# MCU.net
KiCad netlist of a schematic drawn in Altium Designer
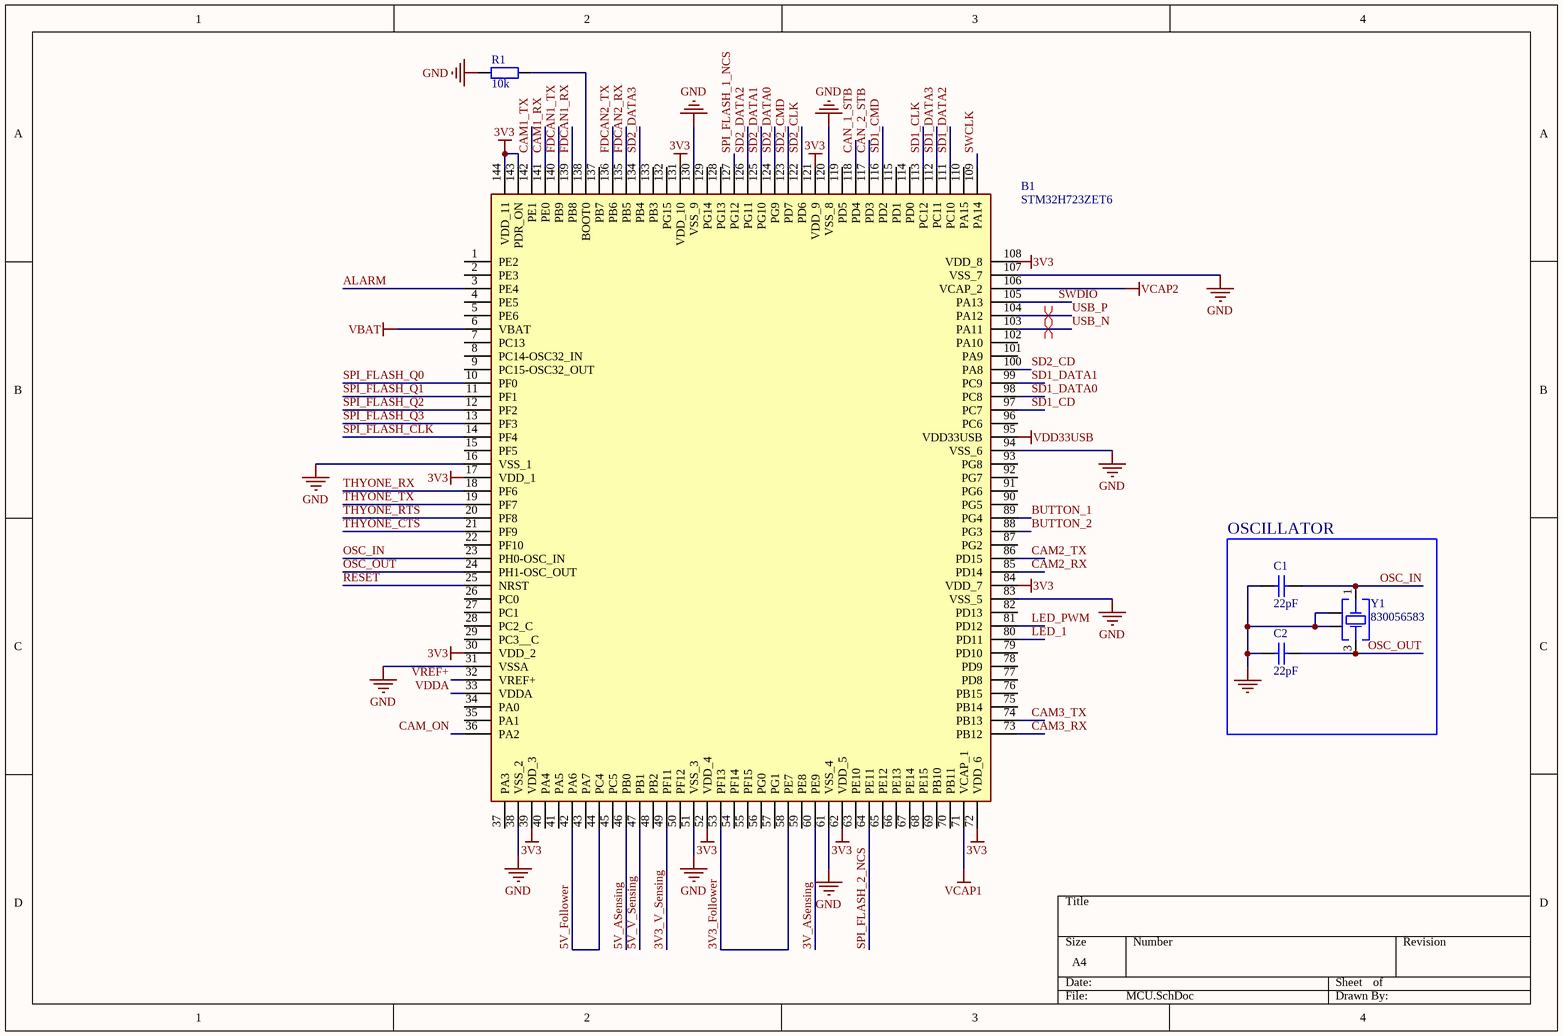
[diagram p0: MCU.SchDoc]

(export (version "E")
  (design (tool "Eeschema 10.0.6"))
  (components
    (comp (ref "B1")
      (value "STM32H723ZET6")
      (footprint "QFP50P2200X2200X160-144N")
      (fields (field (name "MOUSER PART NUMBER") "511-STM32H723ZET6"))
      (libsource (lib "LEEM UPM") (part "STM32H723ZET6"))
    )
    (comp (ref "C1")
      (value "22pF")
      (footprint "WCAP-CSGP_0603_L1.6W0.8H0.8_Reflow")
      (description "WCAP-CSGP Multilayer Ceramic Chip Capacitor, General Purpose, size 0603, NP0, 22pF, 25VDC")
      (fields
        (field (name "MANUFACTURER") "Wurth Elektronik")
        (field (name "MANUFACTURER PART NUMBER") "885012006034")
      )
      (libsource (lib "LEEM UPM") (part "885012209047R"))
    )
    (comp (ref "C2")
      (value "22pF")
      (footprint "WCAP-CSGP_0603_L1.6W0.8H0.8_Reflow")
      (description "WCAP-CSGP Multilayer Ceramic Chip Capacitor, General Purpose, size 0603, NP0, 22pF, 25VDC")
      (fields
        (field (name "MANUFACTURER") "Wurth Elektronik")
        (field (name "MANUFACTURER PART NUMBER") "885012006034")
      )
      (libsource (lib "LEEM UPM") (part "885012209047R"))
    )
    (comp (ref "R1")
      (value "10k")
      (footprint "WRIS-RSKS_0603_Reflow")
      (description "WRIS-RSKS Thick Film Resistor, size 0603, 10000Ohm, 100mW")
      (fields
        (field (name "MANUFACTURER") "Wurth Elektronik")
        (field (name "MANUFACTURER PART NUMBER") "560112116005")
      )
      (libsource (lib "LEEM UPM") (part "560112140010"))
    )
    (comp (ref "Y1")
      (value "830056583")
      (footprint "WE-XTAL_CFPX-104")
      (description "WE-XTAL Quartz Crystal, SMT, CFPX-104, 10MHz, +/-30ppm")
      (fields (field (name "MANUFACTURER") "Wurth Elektronik"))
      (libsource (lib "LEEM UPM") (part "830108161901"))
    )
  )
  (nets
    (net (code "1") (name "/3V3_Follower") (class "Default")
      (node (ref "B1") (pin "53") (pinfunction "PF13_53") (pintype "passive"))
      (node (ref "B1") (pin "58") (pinfunction "PE7_58") (pintype "passive"))
    )
    (net (code "2") (name "/3V3_V_Sensing") (class "Default")
      (node (ref "B1") (pin "49") (pinfunction "PF11_49") (pintype "passive"))
    )
    (net (code "3") (name "/3V_ASensing") (class "Default")
      (node (ref "B1") (pin "60") (pinfunction "PE9_60") (pintype "passive"))
    )
    (net (code "4") (name "/5V_ASensing") (class "Default")
      (node (ref "B1") (pin "46") (pinfunction "PB0_46") (pintype "passive"))
    )
    (net (code "5") (name "/5V_Follower") (class "Default")
      (node (ref "B1") (pin "42") (pinfunction "PA6_42") (pintype "passive"))
      (node (ref "B1") (pin "44") (pinfunction "PC4_44") (pintype "passive"))
    )
    (net (code "6") (name "/5V_V_Sensing") (class "Default")
      (node (ref "B1") (pin "47") (pinfunction "PB1_47") (pintype "passive"))
    )
    (net (code "7") (name "/ALARM") (class "Default")
      (node (ref "B1") (pin "3") (pinfunction "PE4_3") (pintype "passive"))
    )
    (net (code "8") (name "/BUTTON_1") (class "Default")
      (node (ref "B1") (pin "89") (pinfunction "PG4_89") (pintype "passive"))
    )
    (net (code "9") (name "/BUTTON_2") (class "Default")
      (node (ref "B1") (pin "88") (pinfunction "PG3_88") (pintype "passive"))
    )
    (net (code "10") (name "/CAM1_RX") (class "Default")
      (node (ref "B1") (pin "141") (pinfunction "PE0_141") (pintype "passive"))
    )
    (net (code "11") (name "/CAM1_TX") (class "Default")
      (node (ref "B1") (pin "142") (pinfunction "PE1_142") (pintype "passive"))
    )
    (net (code "12") (name "/CAM2_RX") (class "Default")
      (node (ref "B1") (pin "85") (pinfunction "PD14_85") (pintype "passive"))
    )
    (net (code "13") (name "/CAM2_TX") (class "Default")
      (node (ref "B1") (pin "86") (pinfunction "PD15_86") (pintype "passive"))
    )
    (net (code "14") (name "/CAM3_RX") (class "Default")
      (node (ref "B1") (pin "73") (pinfunction "PB12_73") (pintype "passive"))
    )
    (net (code "15") (name "/CAM3_TX") (class "Default")
      (node (ref "B1") (pin "74") (pinfunction "PB13_74") (pintype "passive"))
    )
    (net (code "16") (name "/CAM_ON") (class "Default")
      (node (ref "B1") (pin "36") (pinfunction "PA2_36") (pintype "passive"))
    )
    (net (code "17") (name "/CAN_1_STB") (class "Default")
      (node (ref "B1") (pin "118") (pinfunction "PD4_118") (pintype "passive"))
    )
    (net (code "18") (name "/CAN_2_STB") (class "Default")
      (node (ref "B1") (pin "117") (pinfunction "PD3_117") (pintype "passive"))
    )
    (net (code "19") (name "/FDCAN1_RX") (class "Default")
      (node (ref "B1") (pin "139") (pinfunction "PB8_139") (pintype "passive"))
    )
    (net (code "20") (name "/FDCAN1_TX") (class "Default")
      (node (ref "B1") (pin "140") (pinfunction "PB9_140") (pintype "passive"))
    )
    (net (code "21") (name "/FDCAN2_RX") (class "Default")
      (node (ref "B1") (pin "135") (pinfunction "PB5_135") (pintype "passive"))
    )
    (net (code "22") (name "/FDCAN2_TX") (class "Default")
      (node (ref "B1") (pin "136") (pinfunction "PB6_136") (pintype "passive"))
    )
    (net (code "23") (name "/LED_1") (class "Default")
      (node (ref "B1") (pin "80") (pinfunction "PD11_80") (pintype "passive"))
    )
    (net (code "24") (name "/LED_PWM") (class "Default")
      (node (ref "B1") (pin "81") (pinfunction "PD12_81") (pintype "passive"))
    )
    (net (code "25") (name "/OSC_IN") (class "Default")
      (node (ref "B1") (pin "23") (pinfunction "PH0-OSC_IN_23") (pintype "passive"))
      (node (ref "C1") (pin "1") (pinfunction "1_1") (pintype "passive"))
      (node (ref "Y1") (pin "1") (pinfunction "Crystal_1") (pintype "passive"))
    )
    (net (code "26") (name "/OSC_OUT") (class "Default")
      (node (ref "B1") (pin "24") (pinfunction "PH1-OSC_OUT_24") (pintype "passive"))
      (node (ref "C2") (pin "1") (pinfunction "1_1") (pintype "passive"))
      (node (ref "Y1") (pin "3") (pinfunction "Crystal_3") (pintype "passive"))
    )
    (net (code "27") (name "/RESET") (class "Default")
      (node (ref "B1") (pin "25") (pinfunction "NRST_25") (pintype "passive"))
    )
    (net (code "28") (name "/SD1_CD") (class "Default")
      (node (ref "B1") (pin "97") (pinfunction "PC7_97") (pintype "passive"))
    )
    (net (code "29") (name "/SD1_CLK") (class "Default")
      (node (ref "B1") (pin "113") (pinfunction "PC12_113") (pintype "passive"))
    )
    (net (code "30") (name "/SD1_CMD") (class "Default")
      (node (ref "B1") (pin "116") (pinfunction "PD2_116") (pintype "passive"))
    )
    (net (code "31") (name "/SD1_DATA0") (class "Default")
      (node (ref "B1") (pin "98") (pinfunction "PC8_98") (pintype "passive"))
    )
    (net (code "32") (name "/SD1_DATA1") (class "Default")
      (node (ref "B1") (pin "99") (pinfunction "PC9_99") (pintype "passive"))
    )
    (net (code "33") (name "/SD1_DATA2") (class "Default")
      (node (ref "B1") (pin "111") (pinfunction "PC10_111") (pintype "passive"))
    )
    (net (code "34") (name "/SD1_DATA3") (class "Default")
      (node (ref "B1") (pin "112") (pinfunction "PC11_112") (pintype "passive"))
    )
    (net (code "35") (name "/SD2_CD") (class "Default")
      (node (ref "B1") (pin "100") (pinfunction "PA8_100") (pintype "passive"))
    )
    (net (code "36") (name "/SD2_CLK") (class "Default")
      (node (ref "B1") (pin "122") (pinfunction "PD6_122") (pintype "passive"))
    )
    (net (code "37") (name "/SD2_CMD") (class "Default")
      (node (ref "B1") (pin "123") (pinfunction "PD7_123") (pintype "passive"))
    )
    (net (code "38") (name "/SD2_DATA0") (class "Default")
      (node (ref "B1") (pin "124") (pinfunction "PG9_124") (pintype "passive"))
    )
    (net (code "39") (name "/SD2_DATA1") (class "Default")
      (node (ref "B1") (pin "125") (pinfunction "PG10_125") (pintype "passive"))
    )
    (net (code "40") (name "/SD2_DATA2") (class "Default")
      (node (ref "B1") (pin "126") (pinfunction "PG11_126") (pintype "passive"))
    )
    (net (code "41") (name "/SD2_DATA3") (class "Default")
      (node (ref "B1") (pin "134") (pinfunction "PB4_134") (pintype "passive"))
    )
    (net (code "42") (name "/SPI_FLASH_1_NCS") (class "Default")
      (node (ref "B1") (pin "127") (pinfunction "PG12_127") (pintype "passive"))
    )
    (net (code "43") (name "/SPI_FLASH_2_NCS") (class "Default")
      (node (ref "B1") (pin "64") (pinfunction "PE11_64") (pintype "passive"))
    )
    (net (code "44") (name "/SPI_FLASH_CLK") (class "Default")
      (node (ref "B1") (pin "14") (pinfunction "PF4_14") (pintype "passive"))
    )
    (net (code "45") (name "/SPI_FLASH_Q0") (class "Default")
      (node (ref "B1") (pin "10") (pinfunction "PF0_10") (pintype "passive"))
    )
    (net (code "46") (name "/SPI_FLASH_Q1") (class "Default")
      (node (ref "B1") (pin "11") (pinfunction "PF1_11") (pintype "passive"))
    )
    (net (code "47") (name "/SPI_FLASH_Q2") (class "Default")
      (node (ref "B1") (pin "12") (pinfunction "PF2_12") (pintype "passive"))
    )
    (net (code "48") (name "/SPI_FLASH_Q3") (class "Default")
      (node (ref "B1") (pin "13") (pinfunction "PF3_13") (pintype "passive"))
    )
    (net (code "49") (name "/SWCLK") (class "Default")
      (node (ref "B1") (pin "109") (pinfunction "PA14_109") (pintype "passive"))
    )
    (net (code "50") (name "/SWDIO") (class "Default")
      (node (ref "B1") (pin "105") (pinfunction "PA13_105") (pintype "passive"))
    )
    (net (code "51") (name "/THYONE_CTS") (class "Default")
      (node (ref "B1") (pin "21") (pinfunction "PF9_21") (pintype "passive"))
    )
    (net (code "52") (name "/THYONE_RTS") (class "Default")
      (node (ref "B1") (pin "20") (pinfunction "PF8_20") (pintype "passive"))
    )
    (net (code "53") (name "/THYONE_RX") (class "Default")
      (node (ref "B1") (pin "18") (pinfunction "PF6_18") (pintype "passive"))
    )
    (net (code "54") (name "/THYONE_TX") (class "Default")
      (node (ref "B1") (pin "19") (pinfunction "PF7_19") (pintype "passive"))
    )
    (net (code "55") (name "/USB_N") (class "Default")
      (node (ref "B1") (pin "103") (pinfunction "PA11_103") (pintype "passive"))
    )
    (net (code "56") (name "/USB_P") (class "Default")
      (node (ref "B1") (pin "104") (pinfunction "PA12_104") (pintype "passive"))
    )
    (net (code "57") (name "/VDDA") (class "Default")
      (node (ref "B1") (pin "33") (pinfunction "VDDA_33") (pintype "passive"))
    )
    (net (code "58") (name "/VREF+") (class "Default")
      (node (ref "B1") (pin "32") (pinfunction "VREF+_32") (pintype "passive"))
    )
    (net (code "59") (name "3V3") (class "Default")
      (node (ref "B1") (pin "108") (pinfunction "VDD_8_108") (pintype "passive"))
      (node (ref "B1") (pin "121") (pinfunction "VDD_9_121") (pintype "passive"))
      (node (ref "B1") (pin "131") (pinfunction "VDD_10_131") (pintype "passive"))
      (node (ref "B1") (pin "143") (pinfunction "PDR_ON_143") (pintype "passive"))
      (node (ref "B1") (pin "144") (pinfunction "VDD_11_144") (pintype "passive"))
      (node (ref "B1") (pin "17") (pinfunction "VDD_1_17") (pintype "passive"))
      (node (ref "B1") (pin "30") (pinfunction "VDD_2_30") (pintype "passive"))
      (node (ref "B1") (pin "39") (pinfunction "VDD_3_39") (pintype "passive"))
      (node (ref "B1") (pin "52") (pinfunction "VDD_4_52") (pintype "passive"))
      (node (ref "B1") (pin "62") (pinfunction "VDD_5_62") (pintype "passive"))
      (node (ref "B1") (pin "72") (pinfunction "VDD_6_72") (pintype "passive"))
      (node (ref "B1") (pin "84") (pinfunction "VDD_7_84") (pintype "passive"))
    )
    (net (code "60") (name "GND") (class "Default")
      (node (ref "B1") (pin "107") (pinfunction "VSS_7_107") (pintype "passive"))
      (node (ref "B1") (pin "120") (pinfunction "VSS_8_120") (pintype "passive"))
      (node (ref "B1") (pin "130") (pinfunction "VSS_9_130") (pintype "passive"))
      (node (ref "B1") (pin "16") (pinfunction "VSS_1_16") (pintype "passive"))
      (node (ref "B1") (pin "31") (pinfunction "VSSA_31") (pintype "passive"))
      (node (ref "B1") (pin "38") (pinfunction "VSS_2_38") (pintype "passive"))
      (node (ref "B1") (pin "51") (pinfunction "VSS_3_51") (pintype "passive"))
      (node (ref "B1") (pin "61") (pinfunction "VSS_4_61") (pintype "passive"))
      (node (ref "B1") (pin "83") (pinfunction "VSS_5_83") (pintype "passive"))
      (node (ref "B1") (pin "94") (pinfunction "VSS_6_94") (pintype "passive"))
      (node (ref "C1") (pin "2") (pinfunction "2_2") (pintype "passive"))
      (node (ref "C2") (pin "2") (pinfunction "2_2") (pintype "passive"))
      (node (ref "R1") (pin "2") (pinfunction "2_2") (pintype "passive"))
      (node (ref "Y1") (pin "2") (pinfunction "GND_&_Lid_2") (pintype "passive"))
      (node (ref "Y1") (pin "4") (pinfunction "GND_&_Lid_4") (pintype "passive"))
    )
    (net (code "61") (name "Net-(B1-BOOT0)") (class "Default")
      (node (ref "B1") (pin "138") (pinfunction "BOOT0_138") (pintype "passive"))
      (node (ref "R1") (pin "1") (pinfunction "1_1") (pintype "passive"))
    )
    (net (code "62") (name "VBAT") (class "Default")
      (node (ref "B1") (pin "6") (pinfunction "VBAT_6") (pintype "passive"))
    )
    (net (code "63") (name "VCAP1") (class "Default")
      (node (ref "B1") (pin "71") (pinfunction "VCAP_1_71") (pintype "passive"))
    )
    (net (code "64") (name "VCAP2") (class "Default")
      (node (ref "B1") (pin "106") (pinfunction "VCAP_2_106") (pintype "passive"))
    )
    (net (code "65") (name "VDD33USB") (class "Default")
      (node (ref "B1") (pin "95") (pinfunction "VDD33USB_95") (pintype "passive"))
    )
    (net (code "66") (name "unconnected-(B1-PA0-Pad34)") (class "Default")
      (node (ref "B1") (pin "34") (pinfunction "PA0_34") (pintype "passive"))
    )
    (net (code "67") (name "unconnected-(B1-PA1-Pad35)") (class "Default")
      (node (ref "B1") (pin "35") (pinfunction "PA1_35") (pintype "passive"))
    )
    (net (code "68") (name "unconnected-(B1-PA3-Pad37)") (class "Default")
      (node (ref "B1") (pin "37") (pinfunction "PA3_37") (pintype "passive"))
    )
    (net (code "69") (name "unconnected-(B1-PA4-Pad40)") (class "Default")
      (node (ref "B1") (pin "40") (pinfunction "PA4_40") (pintype "passive"))
    )
    (net (code "70") (name "unconnected-(B1-PA5-Pad41)") (class "Default")
      (node (ref "B1") (pin "41") (pinfunction "PA5_41") (pintype "passive"))
    )
    (net (code "71") (name "unconnected-(B1-PA7-Pad43)") (class "Default")
      (node (ref "B1") (pin "43") (pinfunction "PA7_43") (pintype "passive"))
    )
    (net (code "72") (name "unconnected-(B1-PA9-Pad101)") (class "Default")
      (node (ref "B1") (pin "101") (pinfunction "PA9_101") (pintype "passive"))
    )
    (net (code "73") (name "unconnected-(B1-PA10-Pad102)") (class "Default")
      (node (ref "B1") (pin "102") (pinfunction "PA10_102") (pintype "passive"))
    )
    (net (code "74") (name "unconnected-(B1-PA15-Pad110)") (class "Default")
      (node (ref "B1") (pin "110") (pinfunction "PA15_110") (pintype "passive"))
    )
    (net (code "75") (name "unconnected-(B1-PB2-Pad48)") (class "Default")
      (node (ref "B1") (pin "48") (pinfunction "PB2_48") (pintype "passive"))
    )
    (net (code "76") (name "unconnected-(B1-PB3-Pad133)") (class "Default")
      (node (ref "B1") (pin "133") (pinfunction "PB3_133") (pintype "passive"))
    )
    (net (code "77") (name "unconnected-(B1-PB7-Pad137)") (class "Default")
      (node (ref "B1") (pin "137") (pinfunction "PB7_137") (pintype "passive"))
    )
    (net (code "78") (name "unconnected-(B1-PB10-Pad69)") (class "Default")
      (node (ref "B1") (pin "69") (pinfunction "PB10_69") (pintype "passive"))
    )
    (net (code "79") (name "unconnected-(B1-PB11-Pad70)") (class "Default")
      (node (ref "B1") (pin "70") (pinfunction "PB11_70") (pintype "passive"))
    )
    (net (code "80") (name "unconnected-(B1-PB14-Pad75)") (class "Default")
      (node (ref "B1") (pin "75") (pinfunction "PB14_75") (pintype "passive"))
    )
    (net (code "81") (name "unconnected-(B1-PB15-Pad76)") (class "Default")
      (node (ref "B1") (pin "76") (pinfunction "PB15_76") (pintype "passive"))
    )
    (net (code "82") (name "unconnected-(B1-PC0-Pad26)") (class "Default")
      (node (ref "B1") (pin "26") (pinfunction "PC0_26") (pintype "passive"))
    )
    (net (code "83") (name "unconnected-(B1-PC1-Pad27)") (class "Default")
      (node (ref "B1") (pin "27") (pinfunction "PC1_27") (pintype "passive"))
    )
    (net (code "84") (name "unconnected-(B1-PC2_C-Pad28)") (class "Default")
      (node (ref "B1") (pin "28") (pinfunction "PC2_C_28") (pintype "passive"))
    )
    (net (code "85") (name "unconnected-(B1-PC3__C-Pad29)") (class "Default")
      (node (ref "B1") (pin "29") (pinfunction "PC3__C_29") (pintype "passive"))
    )
    (net (code "86") (name "unconnected-(B1-PC5-Pad45)") (class "Default")
      (node (ref "B1") (pin "45") (pinfunction "PC5_45") (pintype "passive"))
    )
    (net (code "87") (name "unconnected-(B1-PC6-Pad96)") (class "Default")
      (node (ref "B1") (pin "96") (pinfunction "PC6_96") (pintype "passive"))
    )
    (net (code "88") (name "unconnected-(B1-PC13-Pad7)") (class "Default")
      (node (ref "B1") (pin "7") (pinfunction "PC13_7") (pintype "passive"))
    )
    (net (code "89") (name "unconnected-(B1-PC14-OSC32_IN-Pad8)") (class "Default")
      (node (ref "B1") (pin "8") (pinfunction "PC14-OSC32_IN_8") (pintype "passive"))
    )
    (net (code "90") (name "unconnected-(B1-PC15-OSC32_OUT-Pad9)") (class "Default")
      (node (ref "B1") (pin "9") (pinfunction "PC15-OSC32_OUT_9") (pintype "passive"))
    )
    (net (code "91") (name "unconnected-(B1-PD0-Pad114)") (class "Default")
      (node (ref "B1") (pin "114") (pinfunction "PD0_114") (pintype "passive"))
    )
    (net (code "92") (name "unconnected-(B1-PD1-Pad115)") (class "Default")
      (node (ref "B1") (pin "115") (pinfunction "PD1_115") (pintype "passive"))
    )
    (net (code "93") (name "unconnected-(B1-PD5-Pad119)") (class "Default")
      (node (ref "B1") (pin "119") (pinfunction "PD5_119") (pintype "passive"))
    )
    (net (code "94") (name "unconnected-(B1-PD8-Pad77)") (class "Default")
      (node (ref "B1") (pin "77") (pinfunction "PD8_77") (pintype "passive"))
    )
    (net (code "95") (name "unconnected-(B1-PD9-Pad78)") (class "Default")
      (node (ref "B1") (pin "78") (pinfunction "PD9_78") (pintype "passive"))
    )
    (net (code "96") (name "unconnected-(B1-PD10-Pad79)") (class "Default")
      (node (ref "B1") (pin "79") (pinfunction "PD10_79") (pintype "passive"))
    )
    (net (code "97") (name "unconnected-(B1-PD13-Pad82)") (class "Default")
      (node (ref "B1") (pin "82") (pinfunction "PD13_82") (pintype "passive"))
    )
    (net (code "98") (name "unconnected-(B1-PE2-Pad1)") (class "Default")
      (node (ref "B1") (pin "1") (pinfunction "PE2_1") (pintype "passive"))
    )
    (net (code "99") (name "unconnected-(B1-PE3-Pad2)") (class "Default")
      (node (ref "B1") (pin "2") (pinfunction "PE3_2") (pintype "passive"))
    )
    (net (code "100") (name "unconnected-(B1-PE5-Pad4)") (class "Default")
      (node (ref "B1") (pin "4") (pinfunction "PE5_4") (pintype "passive"))
    )
    (net (code "101") (name "unconnected-(B1-PE6-Pad5)") (class "Default")
      (node (ref "B1") (pin "5") (pinfunction "PE6_5") (pintype "passive"))
    )
    (net (code "102") (name "unconnected-(B1-PE8-Pad59)") (class "Default")
      (node (ref "B1") (pin "59") (pinfunction "PE8_59") (pintype "passive"))
    )
    (net (code "103") (name "unconnected-(B1-PE10-Pad63)") (class "Default")
      (node (ref "B1") (pin "63") (pinfunction "PE10_63") (pintype "passive"))
    )
    (net (code "104") (name "unconnected-(B1-PE12-Pad65)") (class "Default")
      (node (ref "B1") (pin "65") (pinfunction "PE12_65") (pintype "passive"))
    )
    (net (code "105") (name "unconnected-(B1-PE13-Pad66)") (class "Default")
      (node (ref "B1") (pin "66") (pinfunction "PE13_66") (pintype "passive"))
    )
    (net (code "106") (name "unconnected-(B1-PE14-Pad67)") (class "Default")
      (node (ref "B1") (pin "67") (pinfunction "PE14_67") (pintype "passive"))
    )
    (net (code "107") (name "unconnected-(B1-PE15-Pad68)") (class "Default")
      (node (ref "B1") (pin "68") (pinfunction "PE15_68") (pintype "passive"))
    )
    (net (code "108") (name "unconnected-(B1-PF5-Pad15)") (class "Default")
      (node (ref "B1") (pin "15") (pinfunction "PF5_15") (pintype "passive"))
    )
    (net (code "109") (name "unconnected-(B1-PF10-Pad22)") (class "Default")
      (node (ref "B1") (pin "22") (pinfunction "PF10_22") (pintype "passive"))
    )
    (net (code "110") (name "unconnected-(B1-PF12-Pad50)") (class "Default")
      (node (ref "B1") (pin "50") (pinfunction "PF12_50") (pintype "passive"))
    )
    (net (code "111") (name "unconnected-(B1-PF14-Pad54)") (class "Default")
      (node (ref "B1") (pin "54") (pinfunction "PF14_54") (pintype "passive"))
    )
    (net (code "112") (name "unconnected-(B1-PF15-Pad55)") (class "Default")
      (node (ref "B1") (pin "55") (pinfunction "PF15_55") (pintype "passive"))
    )
    (net (code "113") (name "unconnected-(B1-PG0-Pad56)") (class "Default")
      (node (ref "B1") (pin "56") (pinfunction "PG0_56") (pintype "passive"))
    )
    (net (code "114") (name "unconnected-(B1-PG1-Pad57)") (class "Default")
      (node (ref "B1") (pin "57") (pinfunction "PG1_57") (pintype "passive"))
    )
    (net (code "115") (name "unconnected-(B1-PG2-Pad87)") (class "Default")
      (node (ref "B1") (pin "87") (pinfunction "PG2_87") (pintype "passive"))
    )
    (net (code "116") (name "unconnected-(B1-PG5-Pad90)") (class "Default")
      (node (ref "B1") (pin "90") (pinfunction "PG5_90") (pintype "passive"))
    )
    (net (code "117") (name "unconnected-(B1-PG6-Pad91)") (class "Default")
      (node (ref "B1") (pin "91") (pinfunction "PG6_91") (pintype "passive"))
    )
    (net (code "118") (name "unconnected-(B1-PG7-Pad92)") (class "Default")
      (node (ref "B1") (pin "92") (pinfunction "PG7_92") (pintype "passive"))
    )
    (net (code "119") (name "unconnected-(B1-PG8-Pad93)") (class "Default")
      (node (ref "B1") (pin "93") (pinfunction "PG8_93") (pintype "passive"))
    )
    (net (code "120") (name "unconnected-(B1-PG13-Pad128)") (class "Default")
      (node (ref "B1") (pin "128") (pinfunction "PG13_128") (pintype "passive"))
    )
    (net (code "121") (name "unconnected-(B1-PG14-Pad129)") (class "Default")
      (node (ref "B1") (pin "129") (pinfunction "PG14_129") (pintype "passive"))
    )
    (net (code "122") (name "unconnected-(B1-PG15-Pad132)") (class "Default")
      (node (ref "B1") (pin "132") (pinfunction "PG15_132") (pintype "passive"))
    )
  )
)
